# dat.net
KiCad netlist of a schematic drawn in Altium Designer
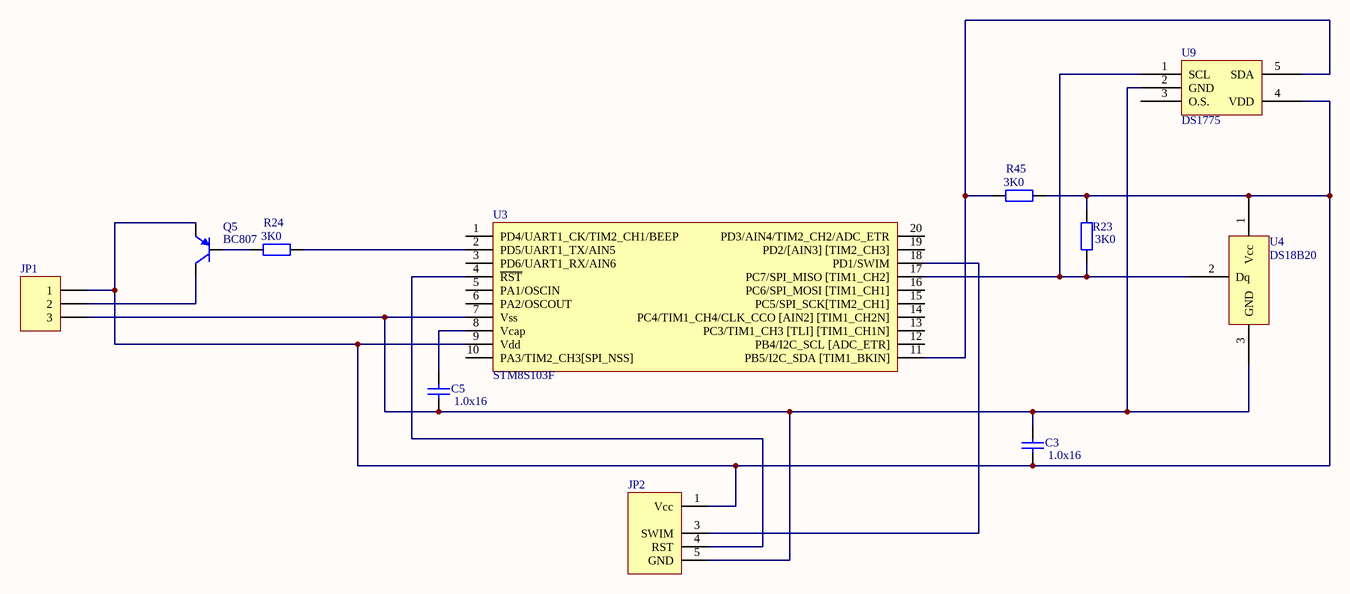
[diagram p0: dat.SchDoc]

(export (version "E")
  (design (tool "Eeschema 10.0.6"))
  (components
    (comp (ref "C3")
      (value "1.0x16")
      (footprint "_1206")
      (description "Capacitor")
      (fields (field (name "MANUFACTURER") "Generic Components") (field (name "PUBLISHER") "Altium Limited"))
      (libsource (lib "Miscellaneous Devices") (part "Cap Semi"))
    )
    (comp (ref "C5")
      (value "1.0x16")
      (footprint "_1206")
      (description "Capacitor")
      (fields (field (name "MANUFACTURER") "Generic Components") (field (name "PUBLISHER") "Altium Limited"))
      (libsource (lib "Miscellaneous Devices") (part "Cap Semi"))
    )
    (comp (ref "JP1")
      (value "DG306-5.0-03P")
      (footprint "BT5-3")
      (description "Header, 3-Pin")
      (fields (field (name "MANUFACTURER") "Generic Components") (field (name "PUBLISHER") "Altium Limited"))
      (libsource (lib "Miscellaneous Connectors") (part "Header 3"))
    )
    (comp (ref "JP2") (value "~") (footprint "HDR1X5_uart") (libsource (lib "PAL") (part "SWIM_CONN")))
    (comp (ref "Q5")
      (value "BC807")
      (footprint "SO-G3")
      (description "General Purpose Transistor PNP Silicon")
      (fields (field (name "MANUFACTURER") "Motorola") (field (name "PUBLISHER") "Altium Limited"))
      (libsource (lib "PAL") (part "BC857ALT1"))
    )
    (comp (ref "R23")
      (value "3K0")
      (footprint "_1206")
      (description "Resistor")
      (fields (field (name "MANUFACTURER") "Generic Components") (field (name "PUBLISHER") "Altium Limited"))
      (libsource (lib "Miscellaneous Devices") (part "Res2"))
    )
    (comp (ref "R24")
      (value "3K0")
      (footprint "_1206")
      (description "Resistor")
      (fields (field (name "MANUFACTURER") "Generic Components") (field (name "PUBLISHER") "Altium Limited"))
      (libsource (lib "") (part "Res2_1"))
    )
    (comp (ref "R45")
      (value "3K0")
      (footprint "_1206")
      (description "Resistor")
      (fields (field (name "MANUFACTURER") "Generic Components") (field (name "PUBLISHER") "Altium Limited"))
      (libsource (lib "") (part "Res2_2"))
    )
    (comp (ref "U3") (value "~") (footprint "TSSO6x6-G20/Y1.6") (libsource (lib "PAL") (part "STM8S103F")))
    (comp (ref "U4") (value "DS18B20") (footprint "DS18B20_H") (libsource (lib "PAL") (part "DS18B20")))
    (comp (ref "U9") (value "DS1775") (footprint "SO-G5/P.95") (libsource (lib "PAL") (part "DS1775")))
  )
  (nets
    (net (code "1") (name "Net-(JP2-GND)") (class "Default")
      (node (ref "C3") (pin "2") (pinfunction "2_2") (pintype "passive"))
      (node (ref "C5") (pin "1") (pinfunction "1_1") (pintype "passive"))
      (node (ref "JP1") (pin "3") (pinfunction "3_3") (pintype "passive"))
      (node (ref "JP2") (pin "5") (pinfunction "GND_5") (pintype "passive"))
      (node (ref "U3") (pin "7") (pinfunction "Vss_7") (pintype "passive"))
      (node (ref "U4") (pin "3") (pinfunction "GND_3") (pintype "passive"))
      (node (ref "U9") (pin "2") (pinfunction "GND_2") (pintype "passive"))
    )
    (net (code "2") (name "Net-(JP2-RST)") (class "Default")
      (node (ref "JP2") (pin "4") (pinfunction "RST_4") (pintype "passive"))
      (node (ref "U3") (pin "4") (pinfunction "~{RST}_4") (pintype "passive"))
    )
    (net (code "3") (name "Net-(JP2-SWIM)") (class "Default")
      (node (ref "JP2") (pin "3") (pinfunction "SWIM_3") (pintype "passive"))
      (node (ref "U3") (pin "18") (pinfunction "PD1/SWIM_18") (pintype "passive"))
    )
    (net (code "4") (name "Net-(JP2-Vcc)") (class "Default")
      (node (ref "C3") (pin "1") (pinfunction "1_1") (pintype "passive"))
      (node (ref "JP1") (pin "1") (pinfunction "1_1") (pintype "passive"))
      (node (ref "JP2") (pin "1") (pinfunction "Vcc_1") (pintype "passive"))
      (node (ref "Q5") (pin "2") (pinfunction "E_2") (pintype "passive"))
      (node (ref "R23") (pin "1") (pinfunction "1_1") (pintype "passive"))
      (node (ref "R45") (pin "2") (pinfunction "2_2") (pintype "passive"))
      (node (ref "U3") (pin "9") (pinfunction "Vdd_9") (pintype "passive"))
      (node (ref "U4") (pin "1") (pinfunction "Vcc_1") (pintype "passive"))
      (node (ref "U9") (pin "4") (pinfunction "VDD_4") (pintype "passive"))
    )
    (net (code "5") (name "Net-(Q5-B)") (class "Default")
      (node (ref "Q5") (pin "1") (pinfunction "B_1") (pintype "passive"))
      (node (ref "R24") (pin "2") (pinfunction "2_2") (pintype "passive"))
    )
    (net (code "6") (name "Net-(Q5-C)") (class "Default")
      (node (ref "JP1") (pin "2") (pinfunction "2_2") (pintype "passive"))
      (node (ref "Q5") (pin "3") (pinfunction "C_3") (pintype "passive"))
    )
    (net (code "7") (name "Net-(U3-PB5{slash}I2C_SDA_[TIM1_BKIN])") (class "Default")
      (node (ref "R45") (pin "1") (pinfunction "1_1") (pintype "passive"))
      (node (ref "U3") (pin "11") (pinfunction "PB5/I2C_SDA_[TIM1_BKIN]_11") (pintype "passive"))
      (node (ref "U9") (pin "5") (pinfunction "SDA_5") (pintype "passive"))
    )
    (net (code "8") (name "Net-(U3-PC7{slash}SPI_MISO_[TIM1_CH2])") (class "Default")
      (node (ref "R23") (pin "2") (pinfunction "2_2") (pintype "passive"))
      (node (ref "U3") (pin "17") (pinfunction "PC7/SPI_MISO_[TIM1_CH2]_17") (pintype "passive"))
      (node (ref "U4") (pin "2") (pinfunction "Dq_2") (pintype "passive"))
      (node (ref "U9") (pin "1") (pinfunction "SCL_1") (pintype "passive"))
    )
    (net (code "9") (name "Net-(U3-PD5{slash}UART1_TX{slash}AIN5)") (class "Default")
      (node (ref "R24") (pin "1") (pinfunction "1_1") (pintype "passive"))
      (node (ref "U3") (pin "2") (pinfunction "PD5/UART1_TX/AIN5_2") (pintype "passive"))
    )
    (net (code "10") (name "Net-(U3-Vcap)") (class "Default")
      (node (ref "C5") (pin "2") (pinfunction "2_2") (pintype "passive"))
      (node (ref "U3") (pin "8") (pinfunction "Vcap_8") (pintype "passive"))
    )
    (net (code "11") (name "unconnected-(U3-PA1{slash}OSCIN-Pad5)") (class "Default")
      (node (ref "U3") (pin "5") (pinfunction "PA1/OSCIN_5") (pintype "passive"))
    )
    (net (code "12") (name "unconnected-(U3-PA2{slash}OSCOUT-Pad6)") (class "Default")
      (node (ref "U3") (pin "6") (pinfunction "PA2/OSCOUT_6") (pintype "passive"))
    )
    (net (code "13") (name "unconnected-(U3-PA3{slash}TIM2_CH3[SPI_NSS]-Pad10)") (class "Default")
      (node (ref "U3") (pin "10") (pinfunction "PA3/TIM2_CH3[SPI_NSS]_10") (pintype "passive"))
    )
    (net (code "14") (name "unconnected-(U3-PB4{slash}I2C_SCL_[ADC_ETR]-Pad12)") (class "Default")
      (node (ref "U3") (pin "12") (pinfunction "PB4/I2C_SCL_[ADC_ETR]_12") (pintype "passive"))
    )
    (net (code "15") (name "unconnected-(U3-PC3{slash}TIM1_CH3_[TLI]_[TIM1_CH1N]-Pad13)") (class "Default")
      (node (ref "U3") (pin "13") (pinfunction "PC3/TIM1_CH3_[TLI]_[TIM1_CH1N]_13") (pintype "passive"))
    )
    (net (code "16") (name "unconnected-(U3-PC4{slash}TIM1_CH4{slash}CLK_CCO_[AIN2]_[TIM1_CH2N]-Pad14)") (class "Default")
      (node (ref "U3") (pin "14") (pinfunction "PC4/TIM1_CH4/CLK_CCO_[AIN2]_[TIM1_CH2N]_14") (pintype "passive"))
    )
    (net (code "17") (name "unconnected-(U3-PC5{slash}SPI_SCK[TIM2_CH1]-Pad15)") (class "Default")
      (node (ref "U3") (pin "15") (pinfunction "PC5/SPI_SCK[TIM2_CH1]_15") (pintype "passive"))
    )
    (net (code "18") (name "unconnected-(U3-PC6{slash}SPI_MOSI_[TIM1_CH1]-Pad16)") (class "Default")
      (node (ref "U3") (pin "16") (pinfunction "PC6/SPI_MOSI_[TIM1_CH1]_16") (pintype "passive"))
    )
    (net (code "19") (name "unconnected-(U3-PD2{slash}[AIN3]_[TIM2_CH3]-Pad19)") (class "Default")
      (node (ref "U3") (pin "19") (pinfunction "PD2/[AIN3]_[TIM2_CH3]_19") (pintype "passive"))
    )
    (net (code "20") (name "unconnected-(U3-PD3{slash}AIN4{slash}TIM2_CH2{slash}ADC_ETR-Pad20)") (class "Default")
      (node (ref "U3") (pin "20") (pinfunction "PD3/AIN4/TIM2_CH2/ADC_ETR_20") (pintype "passive"))
    )
    (net (code "21") (name "unconnected-(U3-PD4{slash}UART1_CK{slash}TIM2_CH1{slash}BEEP-Pad1)") (class "Default")
      (node (ref "U3") (pin "1") (pinfunction "PD4/UART1_CK/TIM2_CH1/BEEP_1") (pintype "passive"))
    )
    (net (code "22") (name "unconnected-(U3-PD6{slash}UART1_RX{slash}AIN6-Pad3)") (class "Default")
      (node (ref "U3") (pin "3") (pinfunction "PD6/UART1_RX/AIN6_3") (pintype "passive"))
    )
    (net (code "23") (name "unconnected-(U9-O.S.-Pad3)") (class "Default")
      (node (ref "U9") (pin "3") (pinfunction "O.S._3") (pintype "passive"))
    )
  )
)
